# Test.net
KiCad netlist of a schematic drawn in EAGLE
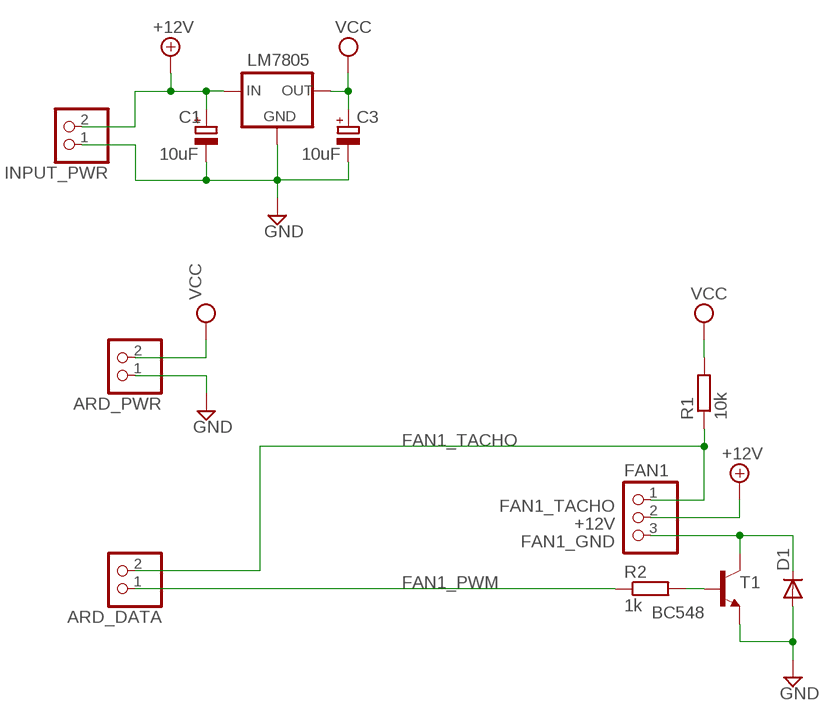
[diagram p0: schematic, sheet 1]

(export (version "E")
  (design (tool "Eeschema 10.0.6"))
  (components
    (comp (ref "ARD_DATA")
      (value "PINHD-1X2")
      (footprint "eagle-import:1X02")
      (libsource (lib "eagle-import") (part "PINHD-1X2"))
    )
    (comp (ref "ARD_PWR")
      (value "PINHD-1X2")
      (footprint "eagle-import:1X02")
      (libsource (lib "eagle-import") (part "PINHD-1X2"))
    )
    (comp (ref "C1")
      (value "10uF")
      (footprint "eagle-import:E2,5-6")
      (libsource (lib "eagle-import") (part "CPOL-EUE2.5-6"))
    )
    (comp (ref "C3")
      (value "10uF")
      (footprint "eagle-import:E2,5-6")
      (libsource (lib "eagle-import") (part "CPOL-EUE2.5-6"))
    )
    (comp (ref "D1")
      (value "DIODE-D-7.5")
      (footprint "eagle-import:D-7.5")
      (libsource (lib "eagle-import") (part "DIODE-D-7.5"))
    )
    (comp (ref "FAN1")
      (value "PINHD-1X3")
      (footprint "eagle-import:1X03")
      (libsource (lib "eagle-import") (part "PINHD-1X3"))
    )
    (comp (ref "INPUT_PWR")
      (value "PINHD-1X2")
      (footprint "eagle-import:1X02")
      (libsource (lib "eagle-import") (part "PINHD-1X2"))
    )
    (comp (ref "LM7805")
      (value "78XXL")
      (footprint "eagle-import:78XXL")
      (libsource (lib "eagle-import") (part "78XXL"))
    )
    (comp (ref "R1")
      (value "10k")
      (footprint "eagle-import:0207_10")
      (libsource (lib "eagle-import") (part "R-EU_0207/10"))
    )
    (comp (ref "R2")
      (value "1k")
      (footprint "eagle-import:0204_7")
      (libsource (lib "eagle-import") (part "R-EU_0204/7"))
    )
    (comp (ref "T1")
      (value "BC548")
      (footprint "eagle-import:TO92")
      (libsource (lib "eagle-import") (part "BC547"))
    )
  )
  (nets
    (net (code "1") (name "+12V") (class "Default")
      (node (ref "C1") (pin "+") (pinfunction "+_+") (pintype "passive"))
      (node (ref "FAN1") (pin "2") (pinfunction "2_2") (pintype "passive"))
      (node (ref "INPUT_PWR") (pin "2") (pinfunction "2_2") (pintype "passive"))
      (node (ref "LM7805") (pin "IN") (pinfunction "IN_IN") (pintype "input"))
    )
    (net (code "2") (name "/FAN1_GND") (class "Default")
      (node (ref "D1") (pin "C") (pinfunction "C_C") (pintype "passive"))
      (node (ref "FAN1") (pin "3") (pinfunction "3_3") (pintype "passive"))
      (node (ref "T1") (pin "3") (pinfunction "C_3") (pintype "passive"))
    )
    (net (code "3") (name "/FAN1_PWM") (class "Default")
      (node (ref "ARD_DATA") (pin "1") (pinfunction "1_1") (pintype "passive"))
      (node (ref "R2") (pin "1") (pinfunction "1_1") (pintype "passive"))
    )
    (net (code "4") (name "/FAN1_TACHO") (class "Default")
      (node (ref "ARD_DATA") (pin "2") (pinfunction "2_2") (pintype "passive"))
      (node (ref "FAN1") (pin "1") (pinfunction "1_1") (pintype "passive"))
      (node (ref "R1") (pin "1") (pinfunction "1_1") (pintype "passive"))
    )
    (net (code "5") (name "GND") (class "Default")
      (node (ref "ARD_PWR") (pin "1") (pinfunction "1_1") (pintype "passive"))
      (node (ref "C1") (pin "-") (pinfunction "-_-") (pintype "passive"))
      (node (ref "C3") (pin "-") (pinfunction "-_-") (pintype "passive"))
      (node (ref "D1") (pin "A") (pinfunction "A_A") (pintype "passive"))
      (node (ref "INPUT_PWR") (pin "1") (pinfunction "1_1") (pintype "passive"))
      (node (ref "LM7805") (pin "GND") (pinfunction "GND_GND") (pintype "input"))
      (node (ref "T1") (pin "1") (pinfunction "E_1") (pintype "passive"))
    )
    (net (code "6") (name "Net-(T1-B)") (class "Default")
      (node (ref "R2") (pin "2") (pinfunction "2_2") (pintype "passive"))
      (node (ref "T1") (pin "2") (pinfunction "B_2") (pintype "passive"))
    )
    (net (code "7") (name "VCC") (class "Default")
      (node (ref "ARD_PWR") (pin "2") (pinfunction "2_2") (pintype "passive"))
      (node (ref "C3") (pin "+") (pinfunction "+_+") (pintype "passive"))
      (node (ref "LM7805") (pin "OUT") (pinfunction "OUT_OUT") (pintype "passive"))
      (node (ref "R1") (pin "2") (pinfunction "2_2") (pintype "passive"))
    )
  )
)
